# 02-POWER.net
KiCad netlist of a schematic drawn in Altium Designer
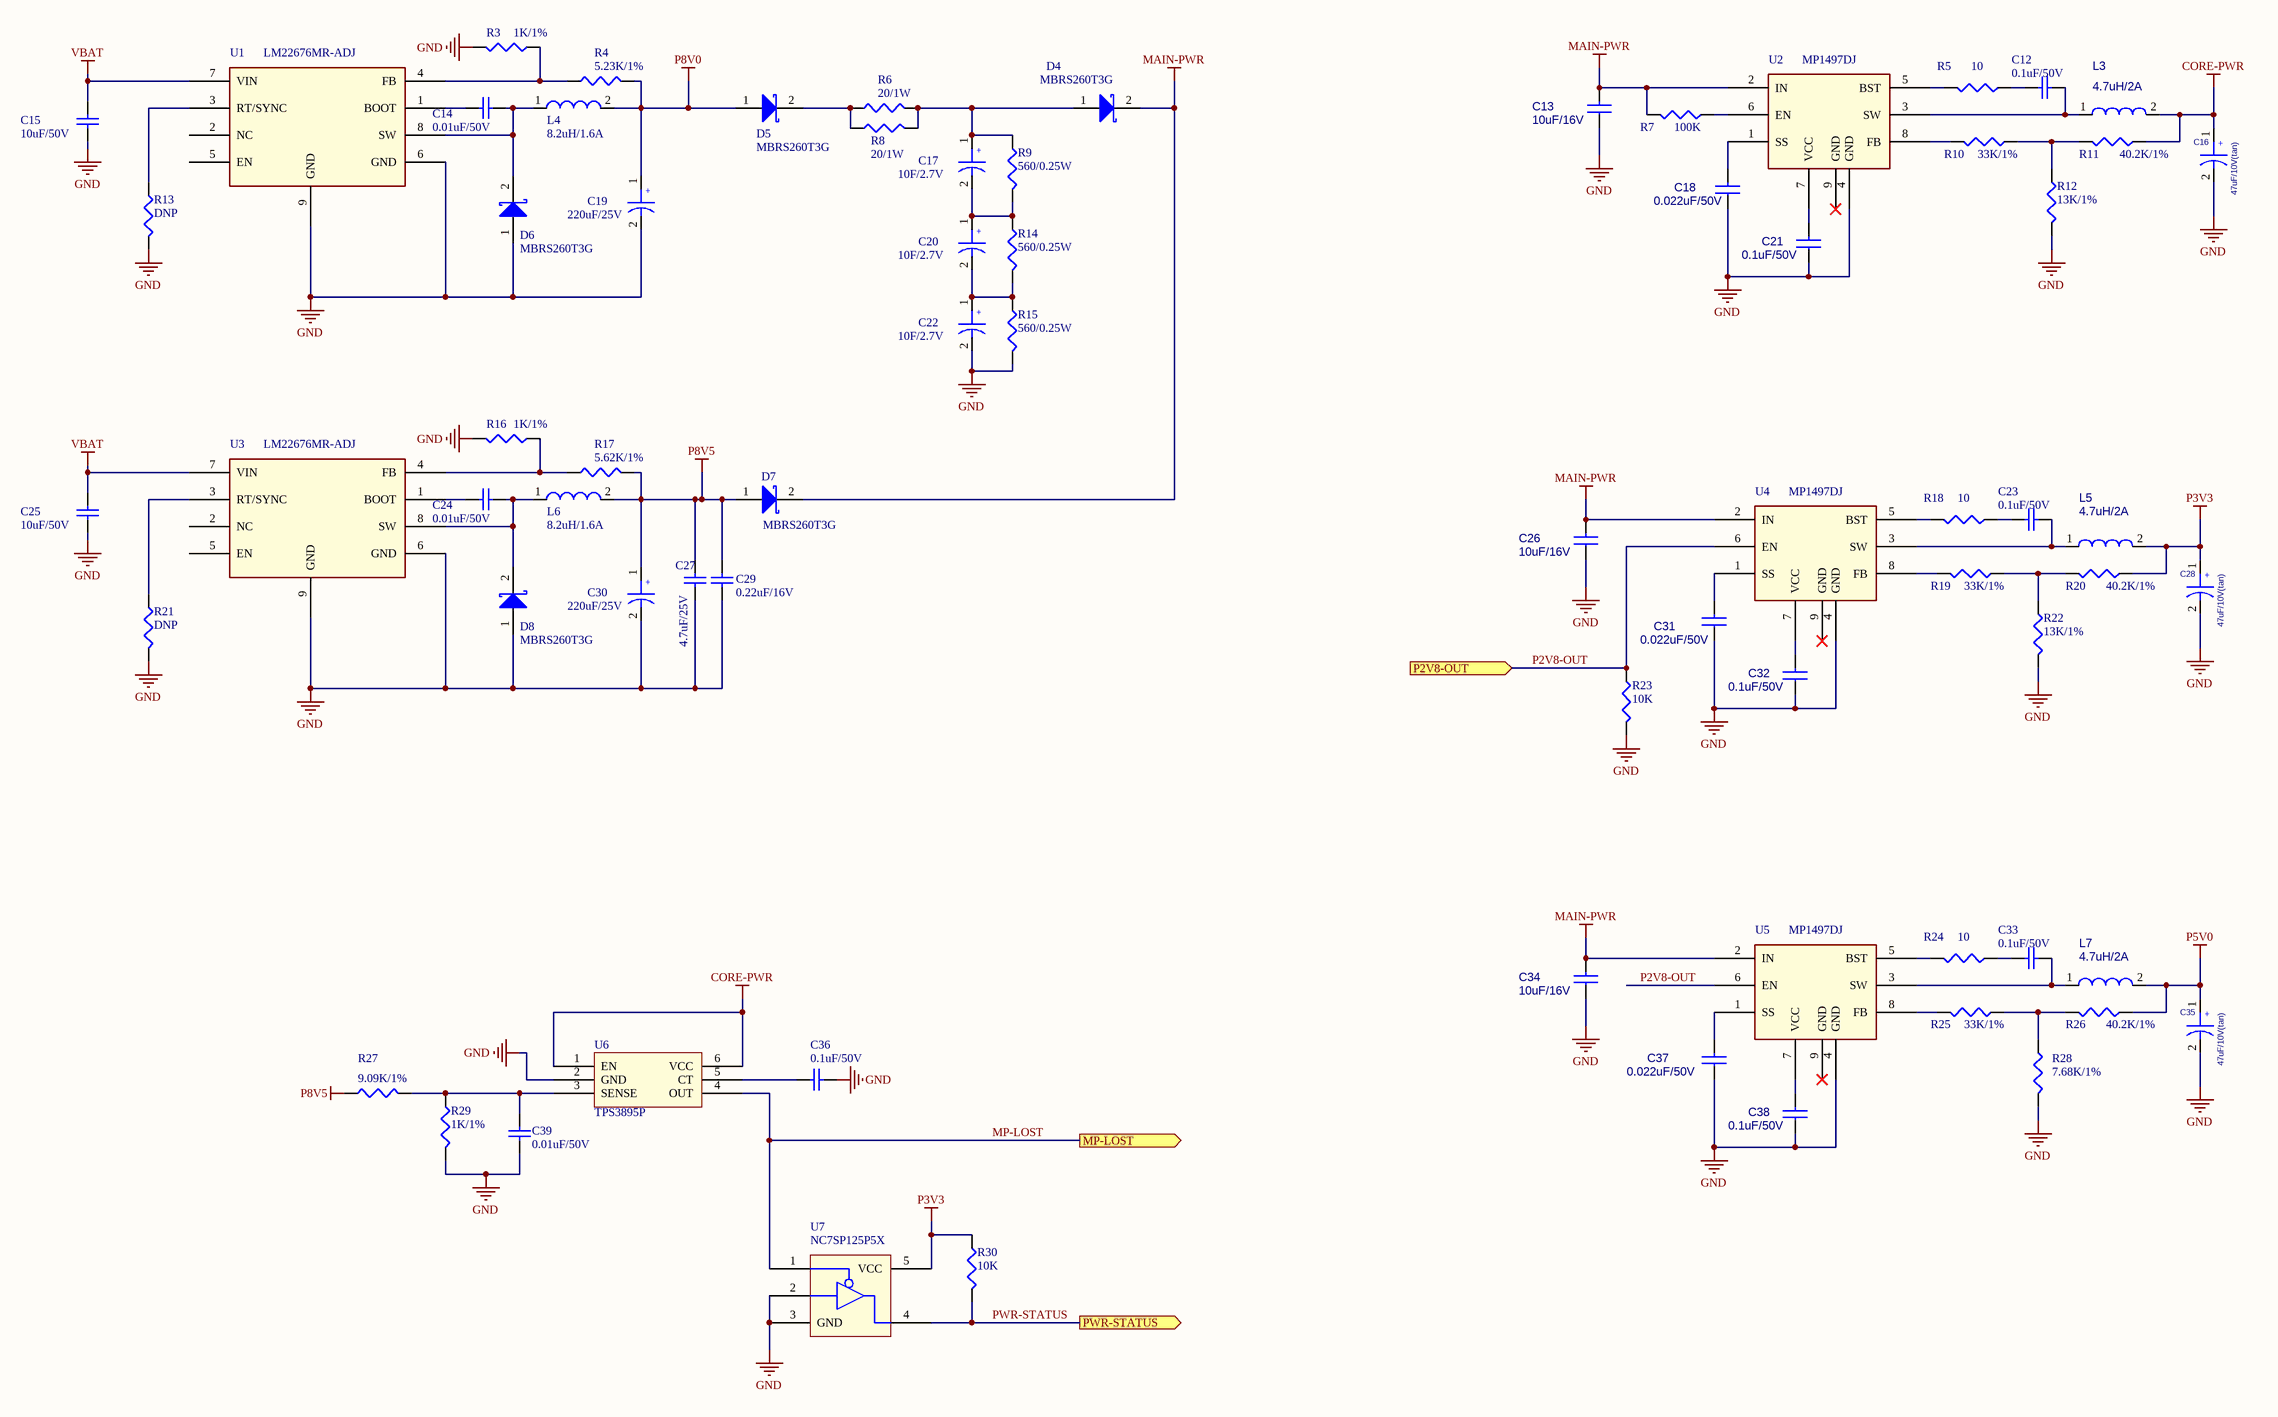
[diagram p0: 02-POWER.SchDoc]

(export (version "E")
  (design (tool "Eeschema 10.0.6"))
  (components
    (comp (ref "C12")
      (value "0.1uF/50V")
      (footprint "0402")
      (description "Capacitor")
      (libsource (lib "Miscellaneous Devices") (part "Cap"))
    )
    (comp (ref "C13") (value "10uF/16V") (footprint "1206") (libsource (lib "*") (part "CAP NP_Dup2")))
    (comp (ref "C14")
      (value "0.01uF/50V")
      (footprint "0402")
      (description "Capacitor")
      (fields (field (name "PUBLISHER") "Altium Limited"))
      (libsource (lib "Miscellaneous Devices") (part "Cap"))
    )
    (comp (ref "C15")
      (value "10uF/50V")
      (footprint "1210")
      (description "Capacitor")
      (fields (field (name "PUBLISHER") "Altium Limited"))
      (libsource (lib "Miscellaneous Devices") (part "Cap"))
    )
    (comp (ref "C16") (value "47uF/10V(tan)") (footprint "3528") (libsource (lib "*") (part "CAP WP")))
    (comp (ref "C17") (value "10F/2.7V") (footprint "SUPERCAP") (libsource (lib "*") (part "CAP WP")))
    (comp (ref "C18") (value "0.022uF/50V") (footprint "0402") (libsource (lib "*") (part "CAP NP_Dup2")))
    (comp (ref "C19") (value "220uF/25V") (footprint "DL-8*10.5") (libsource (lib "*") (part "CAP WP")))
    (comp (ref "C20") (value "10F/2.7V") (footprint "SUPERCAP") (libsource (lib "*") (part "CAP WP")))
    (comp (ref "C21") (value "0.1uF/50V") (footprint "0402") (libsource (lib "*") (part "CAP NP_Dup2")))
    (comp (ref "C22") (value "10F/2.7V") (footprint "SUPERCAP") (libsource (lib "*") (part "CAP WP")))
    (comp (ref "C23")
      (value "0.1uF/50V")
      (footprint "0402")
      (description "Capacitor")
      (libsource (lib "Miscellaneous Devices") (part "Cap"))
    )
    (comp (ref "C24")
      (value "0.01uF/50V")
      (footprint "0402")
      (description "Capacitor")
      (fields (field (name "PUBLISHER") "Altium Limited"))
      (libsource (lib "Miscellaneous Devices") (part "Cap"))
    )
    (comp (ref "C25")
      (value "10uF/50V")
      (footprint "1210")
      (description "Capacitor")
      (fields (field (name "PUBLISHER") "Altium Limited"))
      (libsource (lib "Miscellaneous Devices") (part "Cap"))
    )
    (comp (ref "C26") (value "10uF/16V") (footprint "1206") (libsource (lib "*") (part "CAP NP_Dup2")))
    (comp (ref "C27")
      (value "4.7uF/25V")
      (footprint "0805")
      (description "Capacitor")
      (fields (field (name "PUBLISHER") "Altium Limited"))
      (libsource (lib "Miscellaneous Devices") (part "Cap"))
    )
    (comp (ref "C28") (value "47uF/10V(tan)") (footprint "3528") (libsource (lib "*") (part "CAP WP")))
    (comp (ref "C29")
      (value "0.22uF/16V")
      (footprint "0402")
      (description "Capacitor")
      (fields (field (name "PUBLISHER") "Altium Limited"))
      (libsource (lib "Miscellaneous Devices") (part "Cap"))
    )
    (comp (ref "C30") (value "220uF/25V") (footprint "DL-8*10.5") (libsource (lib "*") (part "CAP WP")))
    (comp (ref "C31") (value "0.022uF/50V") (footprint "0402") (libsource (lib "*") (part "CAP NP_Dup2")))
    (comp (ref "C32") (value "0.1uF/50V") (footprint "0402") (libsource (lib "*") (part "CAP NP_Dup2")))
    (comp (ref "C33")
      (value "0.1uF/50V")
      (footprint "0402")
      (description "Capacitor")
      (libsource (lib "Miscellaneous Devices") (part "Cap"))
    )
    (comp (ref "C34") (value "10uF/16V") (footprint "1206") (libsource (lib "*") (part "CAP NP_Dup2")))
    (comp (ref "C35") (value "47uF/10V(tan)") (footprint "3528") (libsource (lib "*") (part "CAP WP")))
    (comp (ref "C36")
      (value "0.1uF/50V")
      (footprint "0402")
      (description "Capacitor")
      (fields (field (name "PUBLISHER") "Altium Limited"))
      (libsource (lib "Miscellaneous Devices") (part "Cap"))
    )
    (comp (ref "C37") (value "0.022uF/50V") (footprint "0402") (libsource (lib "*") (part "CAP NP_Dup2")))
    (comp (ref "C38") (value "0.1uF/50V") (footprint "0402") (libsource (lib "*") (part "CAP NP_Dup2")))
    (comp (ref "C39")
      (value "0.01uF/50V")
      (footprint "0402")
      (description "Capacitor")
      (fields (field (name "PUBLISHER") "Altium Limited"))
      (libsource (lib "Miscellaneous Devices") (part "Cap"))
    )
    (comp (ref "D4")
      (value "MBRS260T3G")
      (footprint "SMB")
      (description "Schottky Rectifier")
      (libsource (lib "Miscellaneous Devices") (part "Diode 11DQ03"))
    )
    (comp (ref "D5")
      (value "MBRS260T3G")
      (footprint "SMB")
      (description "Schottky Rectifier")
      (libsource (lib "Miscellaneous Devices") (part "Diode 11DQ03"))
    )
    (comp (ref "D6")
      (value "MBRS260T3G")
      (footprint "SMB")
      (description "Schottky Rectifier")
      (libsource (lib "Miscellaneous Devices") (part "Diode 11DQ03"))
    )
    (comp (ref "D7")
      (value "MBRS260T3G")
      (footprint "SMB")
      (description "Schottky Rectifier")
      (libsource (lib "Miscellaneous Devices") (part "Diode 11DQ03"))
    )
    (comp (ref "D8")
      (value "MBRS260T3G")
      (footprint "SMB")
      (description "Schottky Rectifier")
      (libsource (lib "Miscellaneous Devices") (part "Diode 11DQ03"))
    )
    (comp (ref "L3")
      (value "4.7uH/2A")
      (footprint "IND-SMD-5.8*5.8")
      (libsource (lib "*") (part "4.7UH_CDH2D09BNP-4R7MC_0.7A_20%"))
    )
    (comp (ref "L4")
      (value "8.2uH/1.6A")
      (footprint "IND-SMD-5.8*5.8")
      (fields (field (name "PART NUMBER") "SH00000AJ00"))
      (libsource (lib "*") (part "4.7UH_CDH2D09BNP-4R7MC_0.7A_20%"))
    )
    (comp (ref "L5")
      (value "4.7uH/2A")
      (footprint "IND-SMD-5.8*5.8")
      (libsource (lib "*") (part "4.7UH_CDH2D09BNP-4R7MC_0.7A_20%"))
    )
    (comp (ref "L6")
      (value "8.2uH/1.6A")
      (footprint "IND-SMD-5.8*5.8")
      (fields (field (name "PART NUMBER") "SH00000AJ00"))
      (libsource (lib "*") (part "4.7UH_CDH2D09BNP-4R7MC_0.7A_20%"))
    )
    (comp (ref "L7")
      (value "4.7uH/2A")
      (footprint "IND-SMD-5.8*5.8")
      (libsource (lib "*") (part "4.7UH_CDH2D09BNP-4R7MC_0.7A_20%"))
    )
    (comp (ref "R3")
      (value "1K/1%")
      (footprint "0402")
      (description "Resistor")
      (fields (field (name "PUBLISHER") "Altium Limited"))
      (libsource (lib "Miscellaneous Devices") (part "Res3"))
    )
    (comp (ref "R4")
      (value "5.23K/1%")
      (footprint "0402")
      (description "Resistor")
      (fields (field (name "PUBLISHER") "Altium Limited"))
      (libsource (lib "Miscellaneous Devices") (part "Res3"))
    )
    (comp (ref "R5") (value "10") (footprint "0402") (libsource (lib "*") (part "CR16-1003FM")))
    (comp (ref "R6")
      (value "20/1W")
      (footprint "2512")
      (description "Resistor")
      (fields (field (name "PUBLISHER") "Altium Limited"))
      (libsource (lib "Miscellaneous Devices") (part "Res3"))
    )
    (comp (ref "R7") (value "100K") (footprint "0402") (libsource (lib "*") (part "CR16-1003FM")))
    (comp (ref "R8")
      (value "20/1W")
      (footprint "2512")
      (description "Resistor")
      (fields (field (name "PUBLISHER") "Altium Limited"))
      (libsource (lib "Miscellaneous Devices") (part "Res3"))
    )
    (comp (ref "R9")
      (value "560/0.25W")
      (footprint "1206")
      (description "Resistor")
      (fields (field (name "PUBLISHER") "Altium Limited"))
      (libsource (lib "Miscellaneous Devices") (part "Res3"))
    )
    (comp (ref "R10") (value "33K/1%") (footprint "0402") (libsource (lib "*") (part "CR16-1003FM")))
    (comp (ref "R11") (value "40.2K/1%") (footprint "0402") (libsource (lib "*") (part "CR16-1003FM")))
    (comp (ref "R12") (value "13K/1%") (footprint "0402") (libsource (lib "*") (part "CR16-1003FM")))
    (comp (ref "R13")
      (value "DNP")
      (footprint "0402")
      (description "Resistor")
      (fields (field (name "PUBLISHER") "Altium Limited"))
      (libsource (lib "Miscellaneous Devices") (part "Res3"))
    )
    (comp (ref "R14")
      (value "560/0.25W")
      (footprint "1206")
      (description "Resistor")
      (fields (field (name "PUBLISHER") "Altium Limited"))
      (libsource (lib "Miscellaneous Devices") (part "Res3"))
    )
    (comp (ref "R15")
      (value "560/0.25W")
      (footprint "1206")
      (description "Resistor")
      (fields (field (name "PUBLISHER") "Altium Limited"))
      (libsource (lib "Miscellaneous Devices") (part "Res3"))
    )
    (comp (ref "R16")
      (value "1K/1%")
      (footprint "0402")
      (description "Resistor")
      (fields (field (name "PUBLISHER") "Altium Limited"))
      (libsource (lib "Miscellaneous Devices") (part "Res3"))
    )
    (comp (ref "R17")
      (value "5.62K/1%")
      (footprint "0402")
      (description "Resistor")
      (fields (field (name "PUBLISHER") "Altium Limited"))
      (libsource (lib "Miscellaneous Devices") (part "Res3"))
    )
    (comp (ref "R18") (value "10") (footprint "0402") (libsource (lib "*") (part "CR16-1003FM")))
    (comp (ref "R19") (value "33K/1%") (footprint "0402") (libsource (lib "*") (part "CR16-1003FM")))
    (comp (ref "R20") (value "40.2K/1%") (footprint "0402") (libsource (lib "*") (part "CR16-1003FM")))
    (comp (ref "R21")
      (value "DNP")
      (footprint "0402")
      (description "Resistor")
      (fields (field (name "PUBLISHER") "Altium Limited"))
      (libsource (lib "Miscellaneous Devices") (part "Res3"))
    )
    (comp (ref "R22") (value "13K/1%") (footprint "0402") (libsource (lib "*") (part "CR16-1003FM")))
    (comp (ref "R23") (value "10K") (footprint "0402") (libsource (lib "*") (part "CR16-1003FM")))
    (comp (ref "R24") (value "10") (footprint "0402") (libsource (lib "*") (part "CR16-1003FM")))
    (comp (ref "R25") (value "33K/1%") (footprint "0402") (libsource (lib "*") (part "CR16-1003FM")))
    (comp (ref "R26") (value "40.2K/1%") (footprint "0402") (libsource (lib "*") (part "CR16-1003FM")))
    (comp (ref "R27")
      (value "9.09K/1%")
      (footprint "0402")
      (description "Resistor")
      (fields (field (name "PUBLISHER") "Altium Limited"))
      (libsource (lib "Miscellaneous Devices") (part "Res3"))
    )
    (comp (ref "R28") (value "7.68K/1%") (footprint "0402") (libsource (lib "*") (part "CR16-1003FM")))
    (comp (ref "R29")
      (value "1K/1%")
      (footprint "0402")
      (description "Resistor")
      (fields (field (name "PUBLISHER") "Altium Limited"))
      (libsource (lib "Miscellaneous Devices") (part "Res3"))
    )
    (comp (ref "R30") (value "10K") (footprint "0402") (libsource (lib "*") (part "CR16-1003FM")))
    (comp (ref "U1") (value "LM22676MR-ADJ") (libsource (lib "*") (part "LM22670_0")))
    (comp (ref "U2") (value "MP1497DJ") (footprint "TSOT23-8") (libsource (lib "*") (part "MP1482_5")))
    (comp (ref "U3") (value "LM22676MR-ADJ") (libsource (lib "*") (part "LM22670_0")))
    (comp (ref "U4") (value "MP1497DJ") (footprint "TSOT23-8") (libsource (lib "*") (part "MP1482_5")))
    (comp (ref "U5") (value "MP1497DJ") (footprint "TSOT23-8") (libsource (lib "*") (part "MP1482_5")))
    (comp (ref "U6") (value "TPS3895P") (footprint "SON") (libsource (lib "Schlib") (part "TPS3896")))
    (comp (ref "U7") (value "NC7SP125P5X") (footprint "SC70") (libsource (lib "Schlib") (part "NC7SP125P5X")))
  )
  (nets
    (net (code "1") (name "/MP-LOST") (class "Default")
      (node (ref "U6") (pin "4") (pinfunction "OUT_4") (pintype "passive"))
      (node (ref "U7") (pin "1") (pinfunction "OE_1") (pintype "passive"))
    )
    (net (code "2") (name "/P2V8-OUT") (class "Default")
      (node (ref "R23") (pin "1") (pinfunction "1_1") (pintype "passive"))
      (node (ref "U4") (pin "6") (pinfunction "EN_6") (pintype "passive"))
      (node (ref "U5") (pin "6") (pinfunction "EN_6") (pintype "passive"))
    )
    (net (code "3") (name "/PWR-STATUS") (class "Default")
      (node (ref "R30") (pin "2") (pinfunction "2_2") (pintype "passive"))
      (node (ref "U7") (pin "4") (pinfunction "Y_4") (pintype "passive"))
    )
    (net (code "4") (name "CORE-PWR") (class "Default")
      (node (ref "C16") (pin "1") (pinfunction "1_1") (pintype "passive"))
      (node (ref "L3") (pin "2") (pinfunction "2_2") (pintype "passive"))
      (node (ref "R11") (pin "1") (pinfunction "1_1") (pintype "passive"))
      (node (ref "U6") (pin "1") (pinfunction "EN_1") (pintype "passive"))
      (node (ref "U6") (pin "6") (pinfunction "VCC_6") (pintype "passive"))
    )
    (net (code "5") (name "GND") (class "Default")
      (node (ref "C13") (pin "1") (pinfunction "1_1") (pintype "passive"))
      (node (ref "C15") (pin "2") (pinfunction "2_2") (pintype "passive"))
      (node (ref "C16") (pin "2") (pinfunction "2_2") (pintype "passive"))
      (node (ref "C18") (pin "1") (pinfunction "1_1") (pintype "passive"))
      (node (ref "C19") (pin "2") (pinfunction "2_2") (pintype "passive"))
      (node (ref "C21") (pin "1") (pinfunction "1_1") (pintype "passive"))
      (node (ref "C22") (pin "2") (pinfunction "2_2") (pintype "passive"))
      (node (ref "C25") (pin "2") (pinfunction "2_2") (pintype "passive"))
      (node (ref "C26") (pin "1") (pinfunction "1_1") (pintype "passive"))
      (node (ref "C27") (pin "1") (pinfunction "1_1") (pintype "passive"))
      (node (ref "C28") (pin "2") (pinfunction "2_2") (pintype "passive"))
      (node (ref "C29") (pin "1") (pinfunction "1_1") (pintype "passive"))
      (node (ref "C30") (pin "2") (pinfunction "2_2") (pintype "passive"))
      (node (ref "C31") (pin "1") (pinfunction "1_1") (pintype "passive"))
      (node (ref "C32") (pin "1") (pinfunction "1_1") (pintype "passive"))
      (node (ref "C34") (pin "1") (pinfunction "1_1") (pintype "passive"))
      (node (ref "C35") (pin "2") (pinfunction "2_2") (pintype "passive"))
      (node (ref "C36") (pin "2") (pinfunction "2_2") (pintype "passive"))
      (node (ref "C37") (pin "1") (pinfunction "1_1") (pintype "passive"))
      (node (ref "C38") (pin "1") (pinfunction "1_1") (pintype "passive"))
      (node (ref "C39") (pin "2") (pinfunction "2_2") (pintype "passive"))
      (node (ref "D6") (pin "1") (pinfunction "A_1") (pintype "passive"))
      (node (ref "D8") (pin "1") (pinfunction "A_1") (pintype "passive"))
      (node (ref "R12") (pin "2") (pinfunction "2_2") (pintype "passive"))
      (node (ref "R13") (pin "2") (pinfunction "2_2") (pintype "passive"))
      (node (ref "R15") (pin "2") (pinfunction "2_2") (pintype "passive"))
      (node (ref "R16") (pin "2") (pinfunction "2_2") (pintype "passive"))
      (node (ref "R21") (pin "2") (pinfunction "2_2") (pintype "passive"))
      (node (ref "R22") (pin "2") (pinfunction "2_2") (pintype "passive"))
      (node (ref "R23") (pin "2") (pinfunction "2_2") (pintype "passive"))
      (node (ref "R28") (pin "2") (pinfunction "2_2") (pintype "passive"))
      (node (ref "R29") (pin "2") (pinfunction "2_2") (pintype "passive"))
      (node (ref "R3") (pin "2") (pinfunction "2_2") (pintype "passive"))
      (node (ref "U1") (pin "6") (pinfunction "GND_6") (pintype "passive"))
      (node (ref "U1") (pin "9") (pinfunction "GND_9") (pintype "power_in"))
      (node (ref "U2") (pin "4") (pinfunction "GND_4") (pintype "power_in"))
      (node (ref "U3") (pin "6") (pinfunction "GND_6") (pintype "passive"))
      (node (ref "U3") (pin "9") (pinfunction "GND_9") (pintype "power_in"))
      (node (ref "U4") (pin "4") (pinfunction "GND_4") (pintype "power_in"))
      (node (ref "U5") (pin "4") (pinfunction "GND_4") (pintype "power_in"))
      (node (ref "U6") (pin "2") (pinfunction "GND_2") (pintype "passive"))
      (node (ref "U7") (pin "2") (pinfunction "A_2") (pintype "passive"))
      (node (ref "U7") (pin "3") (pinfunction "GND_3") (pintype "passive"))
    )
    (net (code "6") (name "MAIN-PWR") (class "Default")
      (node (ref "C13") (pin "2") (pinfunction "2_2") (pintype "passive"))
      (node (ref "C26") (pin "2") (pinfunction "2_2") (pintype "passive"))
      (node (ref "C34") (pin "2") (pinfunction "2_2") (pintype "passive"))
      (node (ref "D4") (pin "2") (pinfunction "K_2") (pintype "passive"))
      (node (ref "D7") (pin "2") (pinfunction "K_2") (pintype "passive"))
      (node (ref "R7") (pin "2") (pinfunction "2_2") (pintype "passive"))
      (node (ref "U2") (pin "2") (pinfunction "IN_2") (pintype "passive"))
      (node (ref "U4") (pin "2") (pinfunction "IN_2") (pintype "passive"))
      (node (ref "U5") (pin "2") (pinfunction "IN_2") (pintype "passive"))
    )
    (net (code "7") (name "Net-(C12-Pad2)") (class "Default")
      (node (ref "C12") (pin "2") (pinfunction "2_2") (pintype "passive"))
      (node (ref "R5") (pin "1") (pinfunction "1_1") (pintype "passive"))
    )
    (net (code "8") (name "Net-(C17-Pad2)") (class "Default")
      (node (ref "C17") (pin "2") (pinfunction "2_2") (pintype "passive"))
      (node (ref "C20") (pin "1") (pinfunction "1_1") (pintype "passive"))
      (node (ref "R14") (pin "1") (pinfunction "1_1") (pintype "passive"))
      (node (ref "R9") (pin "2") (pinfunction "2_2") (pintype "passive"))
    )
    (net (code "9") (name "Net-(C20-Pad2)") (class "Default")
      (node (ref "C20") (pin "2") (pinfunction "2_2") (pintype "passive"))
      (node (ref "C22") (pin "1") (pinfunction "1_1") (pintype "passive"))
      (node (ref "R14") (pin "2") (pinfunction "2_2") (pintype "passive"))
      (node (ref "R15") (pin "1") (pinfunction "1_1") (pintype "passive"))
    )
    (net (code "10") (name "Net-(C23-Pad2)") (class "Default")
      (node (ref "C23") (pin "2") (pinfunction "2_2") (pintype "passive"))
      (node (ref "R18") (pin "1") (pinfunction "1_1") (pintype "passive"))
    )
    (net (code "11") (name "Net-(C33-Pad2)") (class "Default")
      (node (ref "C33") (pin "2") (pinfunction "2_2") (pintype "passive"))
      (node (ref "R24") (pin "1") (pinfunction "1_1") (pintype "passive"))
    )
    (net (code "12") (name "Net-(D4-A)") (class "Default")
      (node (ref "C17") (pin "1") (pinfunction "1_1") (pintype "passive"))
      (node (ref "D4") (pin "1") (pinfunction "A_1") (pintype "passive"))
      (node (ref "R6") (pin "2") (pinfunction "2_2") (pintype "passive"))
      (node (ref "R8") (pin "2") (pinfunction "2_2") (pintype "passive"))
      (node (ref "R9") (pin "1") (pinfunction "1_1") (pintype "passive"))
    )
    (net (code "13") (name "Net-(D5-K)") (class "Default")
      (node (ref "D5") (pin "2") (pinfunction "K_2") (pintype "passive"))
      (node (ref "R6") (pin "1") (pinfunction "1_1") (pintype "passive"))
      (node (ref "R8") (pin "1") (pinfunction "1_1") (pintype "passive"))
    )
    (net (code "14") (name "Net-(D6-K)") (class "Default")
      (node (ref "C14") (pin "1") (pinfunction "1_1") (pintype "passive"))
      (node (ref "D6") (pin "2") (pinfunction "K_2") (pintype "passive"))
      (node (ref "L4") (pin "1") (pinfunction "1_1") (pintype "passive"))
      (node (ref "U1") (pin "8") (pinfunction "SW_8") (pintype "passive"))
    )
    (net (code "15") (name "Net-(D8-K)") (class "Default")
      (node (ref "C24") (pin "1") (pinfunction "1_1") (pintype "passive"))
      (node (ref "D8") (pin "2") (pinfunction "K_2") (pintype "passive"))
      (node (ref "L6") (pin "1") (pinfunction "1_1") (pintype "passive"))
      (node (ref "U3") (pin "8") (pinfunction "SW_8") (pintype "passive"))
    )
    (net (code "16") (name "Net-(R10-Pad1)") (class "Default")
      (node (ref "R10") (pin "1") (pinfunction "1_1") (pintype "passive"))
      (node (ref "R11") (pin "2") (pinfunction "2_2") (pintype "passive"))
      (node (ref "R12") (pin "1") (pinfunction "1_1") (pintype "passive"))
    )
    (net (code "17") (name "Net-(R19-Pad1)") (class "Default")
      (node (ref "R19") (pin "1") (pinfunction "1_1") (pintype "passive"))
      (node (ref "R20") (pin "2") (pinfunction "2_2") (pintype "passive"))
      (node (ref "R22") (pin "1") (pinfunction "1_1") (pintype "passive"))
    )
    (net (code "18") (name "Net-(R25-Pad1)") (class "Default")
      (node (ref "R25") (pin "1") (pinfunction "1_1") (pintype "passive"))
      (node (ref "R26") (pin "2") (pinfunction "2_2") (pintype "passive"))
      (node (ref "R28") (pin "1") (pinfunction "1_1") (pintype "passive"))
    )
    (net (code "19") (name "Net-(U1-BOOT)") (class "Default")
      (node (ref "C14") (pin "2") (pinfunction "2_2") (pintype "passive"))
      (node (ref "U1") (pin "1") (pinfunction "BOOT_1") (pintype "passive"))
    )
    (net (code "20") (name "Net-(U1-FB)") (class "Default")
      (node (ref "R3") (pin "1") (pinfunction "1_1") (pintype "passive"))
      (node (ref "R4") (pin "1") (pinfunction "1_1") (pintype "passive"))
      (node (ref "U1") (pin "4") (pinfunction "FB_4") (pintype "passive"))
    )
    (net (code "21") (name "Net-(U1-RT{slash}SYNC)") (class "Default")
      (node (ref "R13") (pin "1") (pinfunction "1_1") (pintype "passive"))
      (node (ref "U1") (pin "3") (pinfunction "RT/SYNC_3") (pintype "passive"))
    )
    (net (code "22") (name "Net-(U2-BST)") (class "Default")
      (node (ref "R5") (pin "2") (pinfunction "2_2") (pintype "passive"))
      (node (ref "U2") (pin "5") (pinfunction "BST_5") (pintype "passive"))
    )
    (net (code "23") (name "Net-(U2-EN)") (class "Default")
      (node (ref "R7") (pin "1") (pinfunction "1_1") (pintype "passive"))
      (node (ref "U2") (pin "6") (pinfunction "EN_6") (pintype "passive"))
    )
    (net (code "24") (name "Net-(U2-FB)") (class "Default")
      (node (ref "R10") (pin "2") (pinfunction "2_2") (pintype "passive"))
      (node (ref "U2") (pin "8") (pinfunction "FB_8") (pintype "passive"))
    )
    (net (code "25") (name "Net-(U2-SS)") (class "Default")
      (node (ref "C18") (pin "2") (pinfunction "2_2") (pintype "passive"))
      (node (ref "U2") (pin "1") (pinfunction "SS_1") (pintype "passive"))
    )
    (net (code "26") (name "Net-(U2-SW)") (class "Default")
      (node (ref "C12") (pin "1") (pinfunction "1_1") (pintype "passive"))
      (node (ref "L3") (pin "1") (pinfunction "1_1") (pintype "passive"))
      (node (ref "U2") (pin "3") (pinfunction "SW_3") (pintype "passive"))
    )
    (net (code "27") (name "Net-(U2-VCC)") (class "Default")
      (node (ref "C21") (pin "2") (pinfunction "2_2") (pintype "passive"))
      (node (ref "U2") (pin "7") (pinfunction "VCC_7") (pintype "passive"))
    )
    (net (code "28") (name "Net-(U3-BOOT)") (class "Default")
      (node (ref "C24") (pin "2") (pinfunction "2_2") (pintype "passive"))
      (node (ref "U3") (pin "1") (pinfunction "BOOT_1") (pintype "passive"))
    )
    (net (code "29") (name "Net-(U3-FB)") (class "Default")
      (node (ref "R16") (pin "1") (pinfunction "1_1") (pintype "passive"))
      (node (ref "R17") (pin "1") (pinfunction "1_1") (pintype "passive"))
      (node (ref "U3") (pin "4") (pinfunction "FB_4") (pintype "passive"))
    )
    (net (code "30") (name "Net-(U3-RT{slash}SYNC)") (class "Default")
      (node (ref "R21") (pin "1") (pinfunction "1_1") (pintype "passive"))
      (node (ref "U3") (pin "3") (pinfunction "RT/SYNC_3") (pintype "passive"))
    )
    (net (code "31") (name "Net-(U4-BST)") (class "Default")
      (node (ref "R18") (pin "2") (pinfunction "2_2") (pintype "passive"))
      (node (ref "U4") (pin "5") (pinfunction "BST_5") (pintype "passive"))
    )
    (net (code "32") (name "Net-(U4-FB)") (class "Default")
      (node (ref "R19") (pin "2") (pinfunction "2_2") (pintype "passive"))
      (node (ref "U4") (pin "8") (pinfunction "FB_8") (pintype "passive"))
    )
    (net (code "33") (name "Net-(U4-SS)") (class "Default")
      (node (ref "C31") (pin "2") (pinfunction "2_2") (pintype "passive"))
      (node (ref "U4") (pin "1") (pinfunction "SS_1") (pintype "passive"))
    )
    (net (code "34") (name "Net-(U4-SW)") (class "Default")
      (node (ref "C23") (pin "1") (pinfunction "1_1") (pintype "passive"))
      (node (ref "L5") (pin "1") (pinfunction "1_1") (pintype "passive"))
      (node (ref "U4") (pin "3") (pinfunction "SW_3") (pintype "passive"))
    )
    (net (code "35") (name "Net-(U4-VCC)") (class "Default")
      (node (ref "C32") (pin "2") (pinfunction "2_2") (pintype "passive"))
      (node (ref "U4") (pin "7") (pinfunction "VCC_7") (pintype "passive"))
    )
    (net (code "36") (name "Net-(U5-BST)") (class "Default")
      (node (ref "R24") (pin "2") (pinfunction "2_2") (pintype "passive"))
      (node (ref "U5") (pin "5") (pinfunction "BST_5") (pintype "passive"))
    )
    (net (code "37") (name "Net-(U5-FB)") (class "Default")
      (node (ref "R25") (pin "2") (pinfunction "2_2") (pintype "passive"))
      (node (ref "U5") (pin "8") (pinfunction "FB_8") (pintype "passive"))
    )
    (net (code "38") (name "Net-(U5-SS)") (class "Default")
      (node (ref "C37") (pin "2") (pinfunction "2_2") (pintype "passive"))
      (node (ref "U5") (pin "1") (pinfunction "SS_1") (pintype "passive"))
    )
    (net (code "39") (name "Net-(U5-SW)") (class "Default")
      (node (ref "C33") (pin "1") (pinfunction "1_1") (pintype "passive"))
      (node (ref "L7") (pin "1") (pinfunction "1_1") (pintype "passive"))
      (node (ref "U5") (pin "3") (pinfunction "SW_3") (pintype "passive"))
    )
    (net (code "40") (name "Net-(U5-VCC)") (class "Default")
      (node (ref "C38") (pin "2") (pinfunction "2_2") (pintype "passive"))
      (node (ref "U5") (pin "7") (pinfunction "VCC_7") (pintype "passive"))
    )
    (net (code "41") (name "Net-(U6-CT)") (class "Default")
      (node (ref "C36") (pin "1") (pinfunction "1_1") (pintype "passive"))
      (node (ref "U6") (pin "5") (pinfunction "CT_5") (pintype "passive"))
    )
    (net (code "42") (name "Net-(U6-SENSE)") (class "Default")
      (node (ref "C39") (pin "1") (pinfunction "1_1") (pintype "passive"))
      (node (ref "R27") (pin "2") (pinfunction "2_2") (pintype "passive"))
      (node (ref "R29") (pin "1") (pinfunction "1_1") (pintype "passive"))
      (node (ref "U6") (pin "3") (pinfunction "SENSE_3") (pintype "passive"))
    )
    (net (code "43") (name "P3V3") (class "Default")
      (node (ref "C28") (pin "1") (pinfunction "1_1") (pintype "passive"))
      (node (ref "L5") (pin "2") (pinfunction "2_2") (pintype "passive"))
      (node (ref "R20") (pin "1") (pinfunction "1_1") (pintype "passive"))
      (node (ref "R30") (pin "1") (pinfunction "1_1") (pintype "passive"))
      (node (ref "U7") (pin "5") (pinfunction "VCC_5") (pintype "passive"))
    )
    (net (code "44") (name "P5V0") (class "Default")
      (node (ref "C35") (pin "1") (pinfunction "1_1") (pintype "passive"))
      (node (ref "L7") (pin "2") (pinfunction "2_2") (pintype "passive"))
      (node (ref "R26") (pin "1") (pinfunction "1_1") (pintype "passive"))
    )
    (net (code "45") (name "P8V0") (class "Default")
      (node (ref "C19") (pin "1") (pinfunction "1_1") (pintype "passive"))
      (node (ref "D5") (pin "1") (pinfunction "A_1") (pintype "passive"))
      (node (ref "L4") (pin "2") (pinfunction "2_2") (pintype "passive"))
      (node (ref "R4") (pin "2") (pinfunction "2_2") (pintype "passive"))
    )
    (net (code "46") (name "P8V5") (class "Default")
      (node (ref "C27") (pin "2") (pinfunction "2_2") (pintype "passive"))
      (node (ref "C29") (pin "2") (pinfunction "2_2") (pintype "passive"))
      (node (ref "C30") (pin "1") (pinfunction "1_1") (pintype "passive"))
      (node (ref "D7") (pin "1") (pinfunction "A_1") (pintype "passive"))
      (node (ref "L6") (pin "2") (pinfunction "2_2") (pintype "passive"))
      (node (ref "R17") (pin "2") (pinfunction "2_2") (pintype "passive"))
      (node (ref "R27") (pin "1") (pinfunction "1_1") (pintype "passive"))
    )
    (net (code "47") (name "VBAT") (class "Default")
      (node (ref "C15") (pin "1") (pinfunction "1_1") (pintype "passive"))
      (node (ref "C25") (pin "1") (pinfunction "1_1") (pintype "passive"))
      (node (ref "U1") (pin "7") (pinfunction "VIN_7") (pintype "power_in"))
      (node (ref "U3") (pin "7") (pinfunction "VIN_7") (pintype "power_in"))
    )
    (net (code "48") (name "unconnected-(U1-EN-Pad5)") (class "Default")
      (node (ref "U1") (pin "5") (pinfunction "EN_5") (pintype "passive"))
    )
    (net (code "49") (name "unconnected-(U1-NC-Pad2)") (class "Default")
      (node (ref "U1") (pin "2") (pinfunction "NC_2") (pintype "passive"))
    )
    (net (code "50") (name "unconnected-(U2-GND-Pad9)") (class "Default")
      (node (ref "U2") (pin "9") (pinfunction "GND_9") (pintype "power_in+no_connect"))
    )
    (net (code "51") (name "unconnected-(U3-EN-Pad5)") (class "Default")
      (node (ref "U3") (pin "5") (pinfunction "EN_5") (pintype "passive"))
    )
    (net (code "52") (name "unconnected-(U3-NC-Pad2)") (class "Default")
      (node (ref "U3") (pin "2") (pinfunction "NC_2") (pintype "passive"))
    )
    (net (code "53") (name "unconnected-(U4-GND-Pad9)") (class "Default")
      (node (ref "U4") (pin "9") (pinfunction "GND_9") (pintype "power_in+no_connect"))
    )
    (net (code "54") (name "unconnected-(U5-GND-Pad9)") (class "Default")
      (node (ref "U5") (pin "9") (pinfunction "GND_9") (pintype "power_in+no_connect"))
    )
  )
)
